# 02_-_CPU_-_IO.net
KiCad netlist of a schematic drawn in Altium Designer
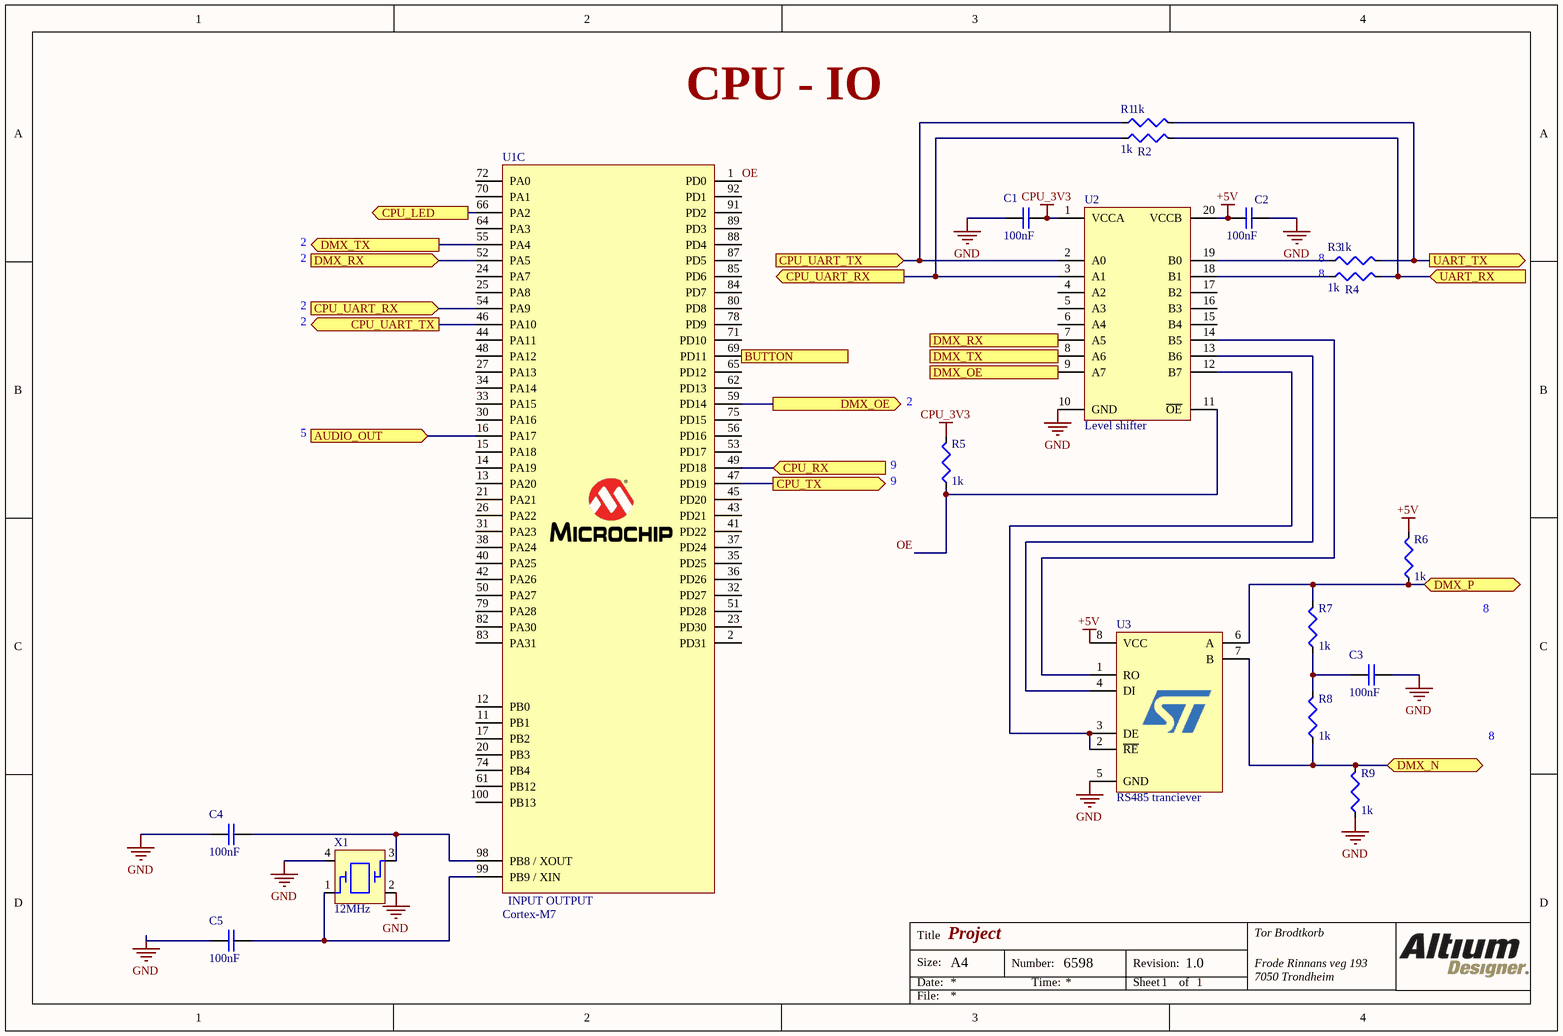
[diagram p0: [02] - CPU - IO.SchDoc]

(export (version "E")
  (design (tool "Eeschema 10.0.6"))
  (components
    (comp (ref "C1")
      (value "100nF")
      (footprint "C0603")
      (description "C0603")
      (fields (field (name "Comment") "02016D104KAT2A"))
      (libsource (lib "Passive components") (part "02016D104KAT2A"))
    )
    (comp (ref "C2")
      (value "100nF")
      (footprint "C0603")
      (description "C0603")
      (fields (field (name "Comment") "02016D104KAT2A"))
      (libsource (lib "Passive components") (part "02016D104KAT2A"))
    )
    (comp (ref "C3")
      (value "100nF")
      (footprint "C0603")
      (description "C0603")
      (fields (field (name "Comment") "02016D104KAT2A"))
      (libsource (lib "Passive components") (part "02016D104KAT2A"))
    )
    (comp (ref "C4")
      (value "100nF")
      (footprint "C0603")
      (description "C0603")
      (fields (field (name "Comment") "02016D104KAT2A"))
      (libsource (lib "Passive components") (part "02016D104KAT2A"))
    )
    (comp (ref "C5")
      (value "100nF")
      (footprint "C0603")
      (description "C0603")
      (fields (field (name "Comment") "02016D104KAT2A"))
      (libsource (lib "Passive components") (part "02016D104KAT2A"))
    )
    (comp (ref "R1")
      (value "1k")
      (footprint "R0603")
      (description "R0603")
      (fields (field (name "Comment") "CPF-A-0603B100KE1"))
      (libsource (lib "Passive components") (part "CPF-A-0603B100KE1"))
    )
    (comp (ref "R2")
      (value "1k")
      (footprint "R0603")
      (description "R0603")
      (fields (field (name "Comment") "CPF-A-0603B100KE1"))
      (libsource (lib "Passive components") (part "CPF-A-0603B100KE1"))
    )
    (comp (ref "R3")
      (value "1k")
      (footprint "R0603")
      (description "R0603")
      (fields (field (name "Comment") "CPF-A-0603B100KE1"))
      (libsource (lib "Passive components") (part "CPF-A-0603B100KE1"))
    )
    (comp (ref "R4")
      (value "1k")
      (footprint "R0603")
      (description "R0603")
      (fields (field (name "Comment") "CPF-A-0603B100KE1"))
      (libsource (lib "Passive components") (part "CPF-A-0603B100KE1"))
    )
    (comp (ref "R5")
      (value "1k")
      (footprint "R0603")
      (description "R0603")
      (fields (field (name "Comment") "CPF-A-0603B100KE1"))
      (libsource (lib "Passive components") (part "CPF-A-0603B100KE1"))
    )
    (comp (ref "R6")
      (value "1k")
      (footprint "R0603")
      (description "R0603")
      (fields (field (name "Comment") "CPF-A-0603B100KE1"))
      (libsource (lib "Passive components") (part "CPF-A-0603B100KE1"))
    )
    (comp (ref "R7")
      (value "1k")
      (footprint "R0603")
      (description "R0603")
      (fields (field (name "Comment") "CPF-A-0603B100KE1"))
      (libsource (lib "Passive components") (part "CPF-A-0603B100KE1"))
    )
    (comp (ref "R8")
      (value "1k")
      (footprint "R0603")
      (description "R0603")
      (fields (field (name "Comment") "CPF-A-0603B100KE1"))
      (libsource (lib "Passive components") (part "CPF-A-0603B100KE1"))
    )
    (comp (ref "R9")
      (value "1k")
      (footprint "R0603")
      (description "R0603")
      (fields (field (name "Comment") "CPF-A-0603B100KE1"))
      (libsource (lib "Passive components") (part "CPF-A-0603B100KE1"))
    )
    (comp (ref "U1")
      (value "Cortex-M7")
      (footprint "ATSAMS70N19A-AN")
      (description "ATSAMS70N19")
      (libsource (lib "Microcontrollers") (part "ATSAMS70N19A-AN"))
    )
    (comp (ref "U2")
      (value "Level shifter")
      (footprint "FXMA108BQX")
      (description "8-bit bidirectional level shifter")
      (libsource (lib "IC") (part "FXMA108BQX"))
    )
    (comp (ref "U3")
      (value "RS485 tranciever")
      (footprint "ST485CDR")
      (libsource (lib "IC") (part "ST485CDR"))
    )
    (comp (ref "X1")
      (value "12MHz")
      (footprint "MCSJK-7U-12.00-12-30-80-B-30")
      (description "Crystal 12MHz 3.2mm x 2.5mm")
      (libsource (lib "Crystals") (part "MCSJK-7U-12.00-12-30-80-B-30"))
    )
  )
  (nets
    (net (code "1") (name "+5V") (class "Default")
      (node (ref "C2") (pin "2") (pinfunction "2_2") (pintype "passive"))
      (node (ref "R6") (pin "2") (pinfunction "2_2") (pintype "passive"))
      (node (ref "U2") (pin "20") (pinfunction "VCCB_20") (pintype "passive"))
      (node (ref "U3") (pin "8") (pinfunction "VCC_8") (pintype "passive"))
    )
    (net (code "2") (name "/AUDIO_OUT") (class "Default")
      (node (ref "U1") (pin "16") (pinfunction "PA17_16") (pintype "passive"))
    )
    (net (code "3") (name "/BUTTON") (class "Default")
      (node (ref "U1") (pin "69") (pinfunction "PD11_69") (pintype "passive"))
    )
    (net (code "4") (name "/CPU_LED") (class "Default")
      (node (ref "U1") (pin "66") (pinfunction "PA2_66") (pintype "passive"))
    )
    (net (code "5") (name "/CPU_RX") (class "Default")
      (node (ref "U1") (pin "49") (pinfunction "PD18_49") (pintype "passive"))
    )
    (net (code "6") (name "/CPU_TX") (class "Default")
      (node (ref "U1") (pin "47") (pinfunction "PD19_47") (pintype "passive"))
    )
    (net (code "7") (name "/CPU_UART_RX") (class "Default")
      (node (ref "R2") (pin "1") (pinfunction "1_1") (pintype "passive"))
      (node (ref "U1") (pin "54") (pinfunction "PA9_54") (pintype "passive"))
      (node (ref "U2") (pin "3") (pinfunction "A1_3") (pintype "passive"))
    )
    (net (code "8") (name "/CPU_UART_TX") (class "Default")
      (node (ref "R1") (pin "1") (pinfunction "1_1") (pintype "passive"))
      (node (ref "U1") (pin "46") (pinfunction "PA10_46") (pintype "passive"))
      (node (ref "U2") (pin "2") (pinfunction "A0_2") (pintype "passive"))
    )
    (net (code "9") (name "/DMX_N") (class "Default")
      (node (ref "R8") (pin "1") (pinfunction "1_1") (pintype "passive"))
      (node (ref "R9") (pin "2") (pinfunction "2_2") (pintype "passive"))
      (node (ref "U3") (pin "7") (pinfunction "B_7") (pintype "passive"))
    )
    (net (code "10") (name "/DMX_OE") (class "Default")
      (node (ref "U1") (pin "59") (pinfunction "PD14_59") (pintype "passive"))
      (node (ref "U2") (pin "9") (pinfunction "A7_9") (pintype "passive"))
    )
    (net (code "11") (name "/DMX_P") (class "Default")
      (node (ref "R6") (pin "1") (pinfunction "1_1") (pintype "passive"))
      (node (ref "R7") (pin "2") (pinfunction "2_2") (pintype "passive"))
      (node (ref "U3") (pin "6") (pinfunction "A_6") (pintype "passive"))
    )
    (net (code "12") (name "/DMX_RX") (class "Default")
      (node (ref "U1") (pin "52") (pinfunction "PA5_52") (pintype "passive"))
      (node (ref "U2") (pin "7") (pinfunction "A5_7") (pintype "passive"))
    )
    (net (code "13") (name "/DMX_TX") (class "Default")
      (node (ref "U1") (pin "55") (pinfunction "PA4_55") (pintype "passive"))
      (node (ref "U2") (pin "8") (pinfunction "A6_8") (pintype "passive"))
    )
    (net (code "14") (name "/OE") (class "Default")
      (node (ref "R5") (pin "1") (pinfunction "1_1") (pintype "passive"))
      (node (ref "U1") (pin "1") (pinfunction "PD0_1") (pintype "passive"))
      (node (ref "U2") (pin "11") (pinfunction "~{OE}_11") (pintype "passive"))
    )
    (net (code "15") (name "/UART_RX") (class "Default")
      (node (ref "R2") (pin "2") (pinfunction "2_2") (pintype "passive"))
      (node (ref "R4") (pin "2") (pinfunction "2_2") (pintype "passive"))
    )
    (net (code "16") (name "/UART_TX") (class "Default")
      (node (ref "R1") (pin "2") (pinfunction "2_2") (pintype "passive"))
      (node (ref "R3") (pin "2") (pinfunction "2_2") (pintype "passive"))
    )
    (net (code "17") (name "CPU_3V3") (class "Default")
      (node (ref "C1") (pin "2") (pinfunction "2_2") (pintype "passive"))
      (node (ref "R5") (pin "2") (pinfunction "2_2") (pintype "passive"))
      (node (ref "U2") (pin "1") (pinfunction "VCCA_1") (pintype "passive"))
    )
    (net (code "18") (name "GND") (class "Default")
      (node (ref "C1") (pin "1") (pinfunction "1_1") (pintype "passive"))
      (node (ref "C2") (pin "1") (pinfunction "1_1") (pintype "passive"))
      (node (ref "C3") (pin "1") (pinfunction "1_1") (pintype "passive"))
      (node (ref "C4") (pin "1") (pinfunction "1_1") (pintype "passive"))
      (node (ref "C5") (pin "1") (pinfunction "1_1") (pintype "passive"))
      (node (ref "R9") (pin "1") (pinfunction "1_1") (pintype "passive"))
      (node (ref "U2") (pin "10") (pinfunction "GND_10") (pintype "passive"))
      (node (ref "U3") (pin "5") (pinfunction "GND_5") (pintype "passive"))
      (node (ref "X1") (pin "2") (pinfunction "2_2") (pintype "passive"))
      (node (ref "X1") (pin "4") (pinfunction "4_4") (pintype "passive"))
    )
    (net (code "19") (name "Net-(C3-Pad2)") (class "Default")
      (node (ref "C3") (pin "2") (pinfunction "2_2") (pintype "passive"))
      (node (ref "R7") (pin "1") (pinfunction "1_1") (pintype "passive"))
      (node (ref "R8") (pin "2") (pinfunction "2_2") (pintype "passive"))
    )
    (net (code "20") (name "Net-(U1C-PB8_{slash}_XOUT)") (class "Default")
      (node (ref "C4") (pin "2") (pinfunction "2_2") (pintype "passive"))
      (node (ref "U1") (pin "98") (pinfunction "PB8_/_XOUT_98") (pintype "passive"))
      (node (ref "X1") (pin "3") (pinfunction "2_3") (pintype "passive"))
    )
    (net (code "21") (name "Net-(U1C-PB9_{slash}_XIN)") (class "Default")
      (node (ref "C5") (pin "2") (pinfunction "2_2") (pintype "passive"))
      (node (ref "U1") (pin "99") (pinfunction "PB9_/_XIN_99") (pintype "passive"))
      (node (ref "X1") (pin "1") (pinfunction "2_1") (pintype "passive"))
    )
    (net (code "22") (name "Net-(U2-B0)") (class "Default")
      (node (ref "R3") (pin "1") (pinfunction "1_1") (pintype "passive"))
      (node (ref "U2") (pin "19") (pinfunction "B0_19") (pintype "passive"))
    )
    (net (code "23") (name "Net-(U2-B1)") (class "Default")
      (node (ref "R4") (pin "1") (pinfunction "1_1") (pintype "passive"))
      (node (ref "U2") (pin "18") (pinfunction "B1_18") (pintype "passive"))
    )
    (net (code "24") (name "Net-(U2-B5)") (class "Default")
      (node (ref "U2") (pin "14") (pinfunction "B5_14") (pintype "passive"))
      (node (ref "U3") (pin "1") (pinfunction "RO_1") (pintype "passive"))
    )
    (net (code "25") (name "Net-(U2-B6)") (class "Default")
      (node (ref "U2") (pin "13") (pinfunction "B6_13") (pintype "passive"))
      (node (ref "U3") (pin "4") (pinfunction "DI_4") (pintype "passive"))
    )
    (net (code "26") (name "Net-(U2-B7)") (class "Default")
      (node (ref "U2") (pin "12") (pinfunction "B7_12") (pintype "passive"))
      (node (ref "U3") (pin "2") (pinfunction "~{RE}_2") (pintype "passive"))
      (node (ref "U3") (pin "3") (pinfunction "DE_3") (pintype "passive"))
    )
    (net (code "27") (name "unconnected-(U1C-PA0-Pad72)") (class "Default")
      (node (ref "U1") (pin "72") (pinfunction "PA0_72") (pintype "passive"))
    )
    (net (code "28") (name "unconnected-(U1C-PA1-Pad70)") (class "Default")
      (node (ref "U1") (pin "70") (pinfunction "PA1_70") (pintype "passive"))
    )
    (net (code "29") (name "unconnected-(U1C-PA3-Pad64)") (class "Default")
      (node (ref "U1") (pin "64") (pinfunction "PA3_64") (pintype "passive"))
    )
    (net (code "30") (name "unconnected-(U1C-PA7-Pad24)") (class "Default")
      (node (ref "U1") (pin "24") (pinfunction "PA7_24") (pintype "passive"))
    )
    (net (code "31") (name "unconnected-(U1C-PA8-Pad25)") (class "Default")
      (node (ref "U1") (pin "25") (pinfunction "PA8_25") (pintype "passive"))
    )
    (net (code "32") (name "unconnected-(U1C-PA11-Pad44)") (class "Default")
      (node (ref "U1") (pin "44") (pinfunction "PA11_44") (pintype "passive"))
    )
    (net (code "33") (name "unconnected-(U1C-PA12-Pad48)") (class "Default")
      (node (ref "U1") (pin "48") (pinfunction "PA12_48") (pintype "passive"))
    )
    (net (code "34") (name "unconnected-(U1C-PA13-Pad27)") (class "Default")
      (node (ref "U1") (pin "27") (pinfunction "PA13_27") (pintype "passive"))
    )
    (net (code "35") (name "unconnected-(U1C-PA14-Pad34)") (class "Default")
      (node (ref "U1") (pin "34") (pinfunction "PA14_34") (pintype "passive"))
    )
    (net (code "36") (name "unconnected-(U1C-PA15-Pad33)") (class "Default")
      (node (ref "U1") (pin "33") (pinfunction "PA15_33") (pintype "passive"))
    )
    (net (code "37") (name "unconnected-(U1C-PA16-Pad30)") (class "Default")
      (node (ref "U1") (pin "30") (pinfunction "PA16_30") (pintype "passive"))
    )
    (net (code "38") (name "unconnected-(U1C-PA18-Pad15)") (class "Default")
      (node (ref "U1") (pin "15") (pinfunction "PA18_15") (pintype "passive"))
    )
    (net (code "39") (name "unconnected-(U1C-PA19-Pad14)") (class "Default")
      (node (ref "U1") (pin "14") (pinfunction "PA19_14") (pintype "passive"))
    )
    (net (code "40") (name "unconnected-(U1C-PA20-Pad13)") (class "Default")
      (node (ref "U1") (pin "13") (pinfunction "PA20_13") (pintype "passive"))
    )
    (net (code "41") (name "unconnected-(U1C-PA21-Pad21)") (class "Default")
      (node (ref "U1") (pin "21") (pinfunction "PA21_21") (pintype "passive"))
    )
    (net (code "42") (name "unconnected-(U1C-PA22-Pad26)") (class "Default")
      (node (ref "U1") (pin "26") (pinfunction "PA22_26") (pintype "passive"))
    )
    (net (code "43") (name "unconnected-(U1C-PA23-Pad31)") (class "Default")
      (node (ref "U1") (pin "31") (pinfunction "PA23_31") (pintype "passive"))
    )
    (net (code "44") (name "unconnected-(U1C-PA24-Pad38)") (class "Default")
      (node (ref "U1") (pin "38") (pinfunction "PA24_38") (pintype "passive"))
    )
    (net (code "45") (name "unconnected-(U1C-PA25-Pad40)") (class "Default")
      (node (ref "U1") (pin "40") (pinfunction "PA25_40") (pintype "passive"))
    )
    (net (code "46") (name "unconnected-(U1C-PA26-Pad42)") (class "Default")
      (node (ref "U1") (pin "42") (pinfunction "PA26_42") (pintype "passive"))
    )
    (net (code "47") (name "unconnected-(U1C-PA27-Pad50)") (class "Default")
      (node (ref "U1") (pin "50") (pinfunction "PA27_50") (pintype "passive"))
    )
    (net (code "48") (name "unconnected-(U1C-PA28-Pad79)") (class "Default")
      (node (ref "U1") (pin "79") (pinfunction "PA28_79") (pintype "passive"))
    )
    (net (code "49") (name "unconnected-(U1C-PA30-Pad82)") (class "Default")
      (node (ref "U1") (pin "82") (pinfunction "PA30_82") (pintype "passive"))
    )
    (net (code "50") (name "unconnected-(U1C-PA31-Pad83)") (class "Default")
      (node (ref "U1") (pin "83") (pinfunction "PA31_83") (pintype "passive"))
    )
    (net (code "51") (name "unconnected-(U1C-PB0-Pad12)") (class "Default")
      (node (ref "U1") (pin "12") (pinfunction "PB0_12") (pintype "passive"))
    )
    (net (code "52") (name "unconnected-(U1C-PB1-Pad11)") (class "Default")
      (node (ref "U1") (pin "11") (pinfunction "PB1_11") (pintype "passive"))
    )
    (net (code "53") (name "unconnected-(U1C-PB2-Pad17)") (class "Default")
      (node (ref "U1") (pin "17") (pinfunction "PB2_17") (pintype "passive"))
    )
    (net (code "54") (name "unconnected-(U1C-PB3-Pad20)") (class "Default")
      (node (ref "U1") (pin "20") (pinfunction "PB3_20") (pintype "passive"))
    )
    (net (code "55") (name "unconnected-(U1C-PB4-Pad74)") (class "Default")
      (node (ref "U1") (pin "74") (pinfunction "PB4_74") (pintype "passive"))
    )
    (net (code "56") (name "unconnected-(U1C-PB12-Pad61)") (class "Default")
      (node (ref "U1") (pin "61") (pinfunction "PB12_61") (pintype "passive"))
    )
    (net (code "57") (name "unconnected-(U1C-PB13-Pad100)") (class "Default")
      (node (ref "U1") (pin "100") (pinfunction "PB13_100") (pintype "passive"))
    )
    (net (code "58") (name "unconnected-(U1C-PD1-Pad92)") (class "Default")
      (node (ref "U1") (pin "92") (pinfunction "PD1_92") (pintype "passive"))
    )
    (net (code "59") (name "unconnected-(U1C-PD2-Pad91)") (class "Default")
      (node (ref "U1") (pin "91") (pinfunction "PD2_91") (pintype "passive"))
    )
    (net (code "60") (name "unconnected-(U1C-PD3-Pad89)") (class "Default")
      (node (ref "U1") (pin "89") (pinfunction "PD3_89") (pintype "passive"))
    )
    (net (code "61") (name "unconnected-(U1C-PD4-Pad88)") (class "Default")
      (node (ref "U1") (pin "88") (pinfunction "PD4_88") (pintype "passive"))
    )
    (net (code "62") (name "unconnected-(U1C-PD5-Pad87)") (class "Default")
      (node (ref "U1") (pin "87") (pinfunction "PD5_87") (pintype "passive"))
    )
    (net (code "63") (name "unconnected-(U1C-PD6-Pad85)") (class "Default")
      (node (ref "U1") (pin "85") (pinfunction "PD6_85") (pintype "passive"))
    )
    (net (code "64") (name "unconnected-(U1C-PD7-Pad84)") (class "Default")
      (node (ref "U1") (pin "84") (pinfunction "PD7_84") (pintype "passive"))
    )
    (net (code "65") (name "unconnected-(U1C-PD8-Pad80)") (class "Default")
      (node (ref "U1") (pin "80") (pinfunction "PD8_80") (pintype "passive"))
    )
    (net (code "66") (name "unconnected-(U1C-PD9-Pad78)") (class "Default")
      (node (ref "U1") (pin "78") (pinfunction "PD9_78") (pintype "passive"))
    )
    (net (code "67") (name "unconnected-(U1C-PD10-Pad71)") (class "Default")
      (node (ref "U1") (pin "71") (pinfunction "PD10_71") (pintype "passive"))
    )
    (net (code "68") (name "unconnected-(U1C-PD12-Pad65)") (class "Default")
      (node (ref "U1") (pin "65") (pinfunction "PD12_65") (pintype "passive"))
    )
    (net (code "69") (name "unconnected-(U1C-PD13-Pad62)") (class "Default")
      (node (ref "U1") (pin "62") (pinfunction "PD13_62") (pintype "passive"))
    )
    (net (code "70") (name "unconnected-(U1C-PD15-Pad75)") (class "Default")
      (node (ref "U1") (pin "75") (pinfunction "PD15_75") (pintype "passive"))
    )
    (net (code "71") (name "unconnected-(U1C-PD16-Pad56)") (class "Default")
      (node (ref "U1") (pin "56") (pinfunction "PD16_56") (pintype "passive"))
    )
    (net (code "72") (name "unconnected-(U1C-PD17-Pad53)") (class "Default")
      (node (ref "U1") (pin "53") (pinfunction "PD17_53") (pintype "passive"))
    )
    (net (code "73") (name "unconnected-(U1C-PD20-Pad45)") (class "Default")
      (node (ref "U1") (pin "45") (pinfunction "PD20_45") (pintype "passive"))
    )
    (net (code "74") (name "unconnected-(U1C-PD21-Pad43)") (class "Default")
      (node (ref "U1") (pin "43") (pinfunction "PD21_43") (pintype "passive"))
    )
    (net (code "75") (name "unconnected-(U1C-PD22-Pad41)") (class "Default")
      (node (ref "U1") (pin "41") (pinfunction "PD22_41") (pintype "passive"))
    )
    (net (code "76") (name "unconnected-(U1C-PD24-Pad37)") (class "Default")
      (node (ref "U1") (pin "37") (pinfunction "PD24_37") (pintype "passive"))
    )
    (net (code "77") (name "unconnected-(U1C-PD25-Pad35)") (class "Default")
      (node (ref "U1") (pin "35") (pinfunction "PD25_35") (pintype "passive"))
    )
    (net (code "78") (name "unconnected-(U1C-PD26-Pad36)") (class "Default")
      (node (ref "U1") (pin "36") (pinfunction "PD26_36") (pintype "passive"))
    )
    (net (code "79") (name "unconnected-(U1C-PD27-Pad32)") (class "Default")
      (node (ref "U1") (pin "32") (pinfunction "PD27_32") (pintype "passive"))
    )
    (net (code "80") (name "unconnected-(U1C-PD28-Pad51)") (class "Default")
      (node (ref "U1") (pin "51") (pinfunction "PD28_51") (pintype "passive"))
    )
    (net (code "81") (name "unconnected-(U1C-PD30-Pad23)") (class "Default")
      (node (ref "U1") (pin "23") (pinfunction "PD30_23") (pintype "passive"))
    )
    (net (code "82") (name "unconnected-(U1C-PD31-Pad2)") (class "Default")
      (node (ref "U1") (pin "2") (pinfunction "PD31_2") (pintype "passive"))
    )
    (net (code "83") (name "unconnected-(U2-A2-Pad4)") (class "Default")
      (node (ref "U2") (pin "4") (pinfunction "A2_4") (pintype "passive"))
    )
    (net (code "84") (name "unconnected-(U2-A3-Pad5)") (class "Default")
      (node (ref "U2") (pin "5") (pinfunction "A3_5") (pintype "passive"))
    )
    (net (code "85") (name "unconnected-(U2-A4-Pad6)") (class "Default")
      (node (ref "U2") (pin "6") (pinfunction "A4_6") (pintype "passive"))
    )
    (net (code "86") (name "unconnected-(U2-B2-Pad17)") (class "Default")
      (node (ref "U2") (pin "17") (pinfunction "B2_17") (pintype "passive"))
    )
    (net (code "87") (name "unconnected-(U2-B3-Pad16)") (class "Default")
      (node (ref "U2") (pin "16") (pinfunction "B3_16") (pintype "passive"))
    )
    (net (code "88") (name "unconnected-(U2-B4-Pad15)") (class "Default")
      (node (ref "U2") (pin "15") (pinfunction "B4_15") (pintype "passive"))
    )
  )
)
